# whey-pendant-revA.net
KiCad netlist of a schematic drawn in EAGLE
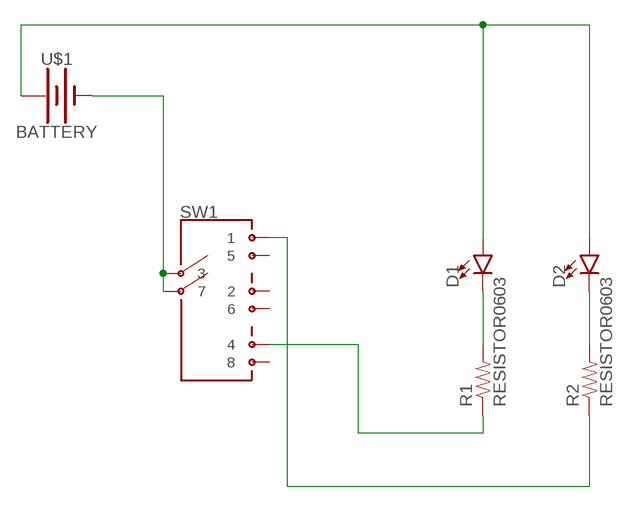
[diagram p0: schematic, sheet 1]

(export (version "E")
  (design (tool "Eeschema 10.0.6"))
  (components
    (comp (ref "D1")
      (value "LED1206")
      (footprint "eagle-import:LED-1206")
      (libsource (lib "eagle-import") (part "LED1206"))
    )
    (comp (ref "D2")
      (value "LED1206")
      (footprint "eagle-import:LED-1206")
      (libsource (lib "eagle-import") (part "LED1206"))
    )
    (comp (ref "R1")
      (value "RESISTOR0603")
      (footprint "eagle-import:R0603")
      (libsource (lib "eagle-import") (part "RESISTOR0603"))
    )
    (comp (ref "R2")
      (value "RESISTOR0603")
      (footprint "eagle-import:R0603")
      (libsource (lib "eagle-import") (part "RESISTOR0603"))
    )
    (comp (ref "SW1")
      (value "JS203011JCQN")
      (footprint "eagle-import:JS203011JCQN")
      (libsource (lib "eagle-import") (part "JS203011JCQN"))
    )
    (comp (ref "U$1")
      (value "BATTERY")
      (footprint "eagle-import:COINCELL16")
      (libsource (lib "eagle-import") (part "BATTERY"))
    )
  )
  (nets
    (net (code "1") (name "Net-(D1-PadA)") (class "Default")
      (node (ref "D1") (pin "A") (pinfunction "A_A") (pintype "passive"))
      (node (ref "D2") (pin "A") (pinfunction "A_A") (pintype "passive"))
      (node (ref "U$1") (pin "P$1") (pinfunction "+_P$1") (pintype "power_in"))
      (node (ref "U$1") (pin "P$2") (pinfunction "+_P$2") (pintype "power_in"))
    )
    (net (code "2") (name "Net-(D1-PadC)") (class "Default")
      (node (ref "D1") (pin "C") (pinfunction "C_C") (pintype "passive"))
      (node (ref "R1") (pin "2") (pinfunction "2_2") (pintype "passive"))
    )
    (net (code "3") (name "Net-(D2-PadC)") (class "Default")
      (node (ref "D2") (pin "C") (pinfunction "C_C") (pintype "passive"))
      (node (ref "R2") (pin "2") (pinfunction "2_2") (pintype "passive"))
    )
    (net (code "4") (name "Net-(R1-Pad1)") (class "Default")
      (node (ref "R1") (pin "1") (pinfunction "1_1") (pintype "passive"))
      (node (ref "SW1") (pin "4") (pinfunction "4_4") (pintype "bidirectional"))
    )
    (net (code "5") (name "Net-(R2-Pad1)") (class "Default")
      (node (ref "R2") (pin "1") (pinfunction "1_1") (pintype "passive"))
      (node (ref "SW1") (pin "1") (pinfunction "1_1") (pintype "bidirectional"))
    )
    (net (code "6") (name "Net-(U$1--)") (class "Default")
      (node (ref "SW1") (pin "3") (pinfunction "3_3") (pintype "bidirectional"))
      (node (ref "SW1") (pin "7") (pinfunction "7_7") (pintype "bidirectional"))
      (node (ref "U$1") (pin "P$3") (pinfunction "-_P$3") (pintype "power_in"))
    )
    (net (code "7") (name "unconnected-(SW1-Pad2)") (class "Default")
      (node (ref "SW1") (pin "2") (pinfunction "2_2") (pintype "bidirectional"))
    )
    (net (code "8") (name "unconnected-(SW1-Pad5)") (class "Default")
      (node (ref "SW1") (pin "5") (pinfunction "5_5") (pintype "bidirectional"))
    )
    (net (code "9") (name "unconnected-(SW1-Pad6)") (class "Default")
      (node (ref "SW1") (pin "6") (pinfunction "6_6") (pintype "bidirectional"))
    )
    (net (code "10") (name "unconnected-(SW1-Pad8)") (class "Default")
      (node (ref "SW1") (pin "8") (pinfunction "8_8") (pintype "bidirectional"))
    )
  )
)
